# GMSL_DESERIALIZER.net
KiCad netlist of a schematic drawn in Altium Designer
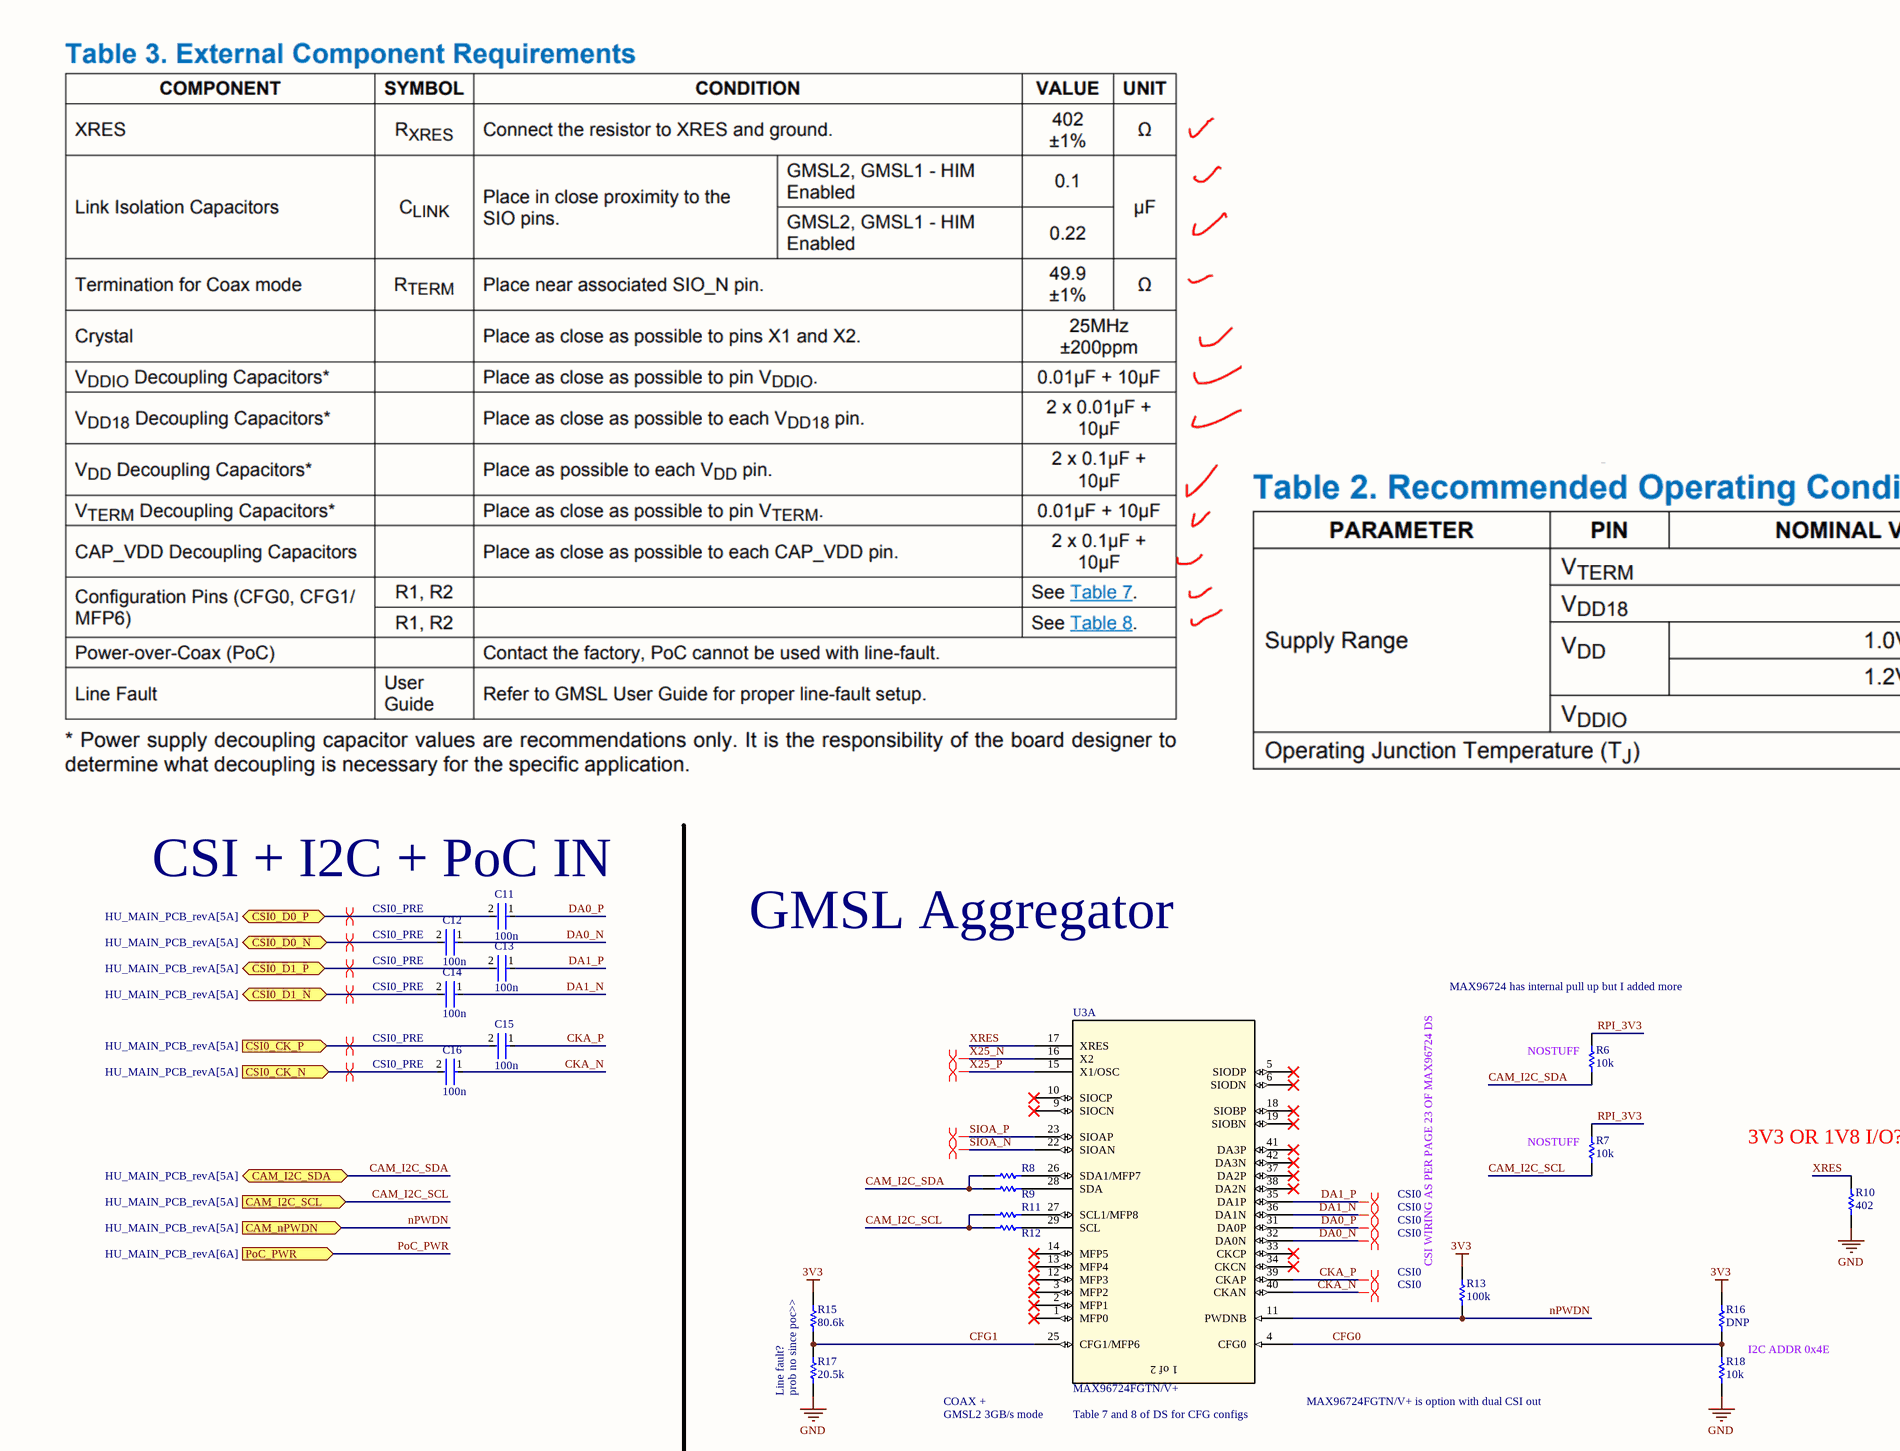
[diagram p0: GMSL_DESERIALIZER.SchDoc, top left]
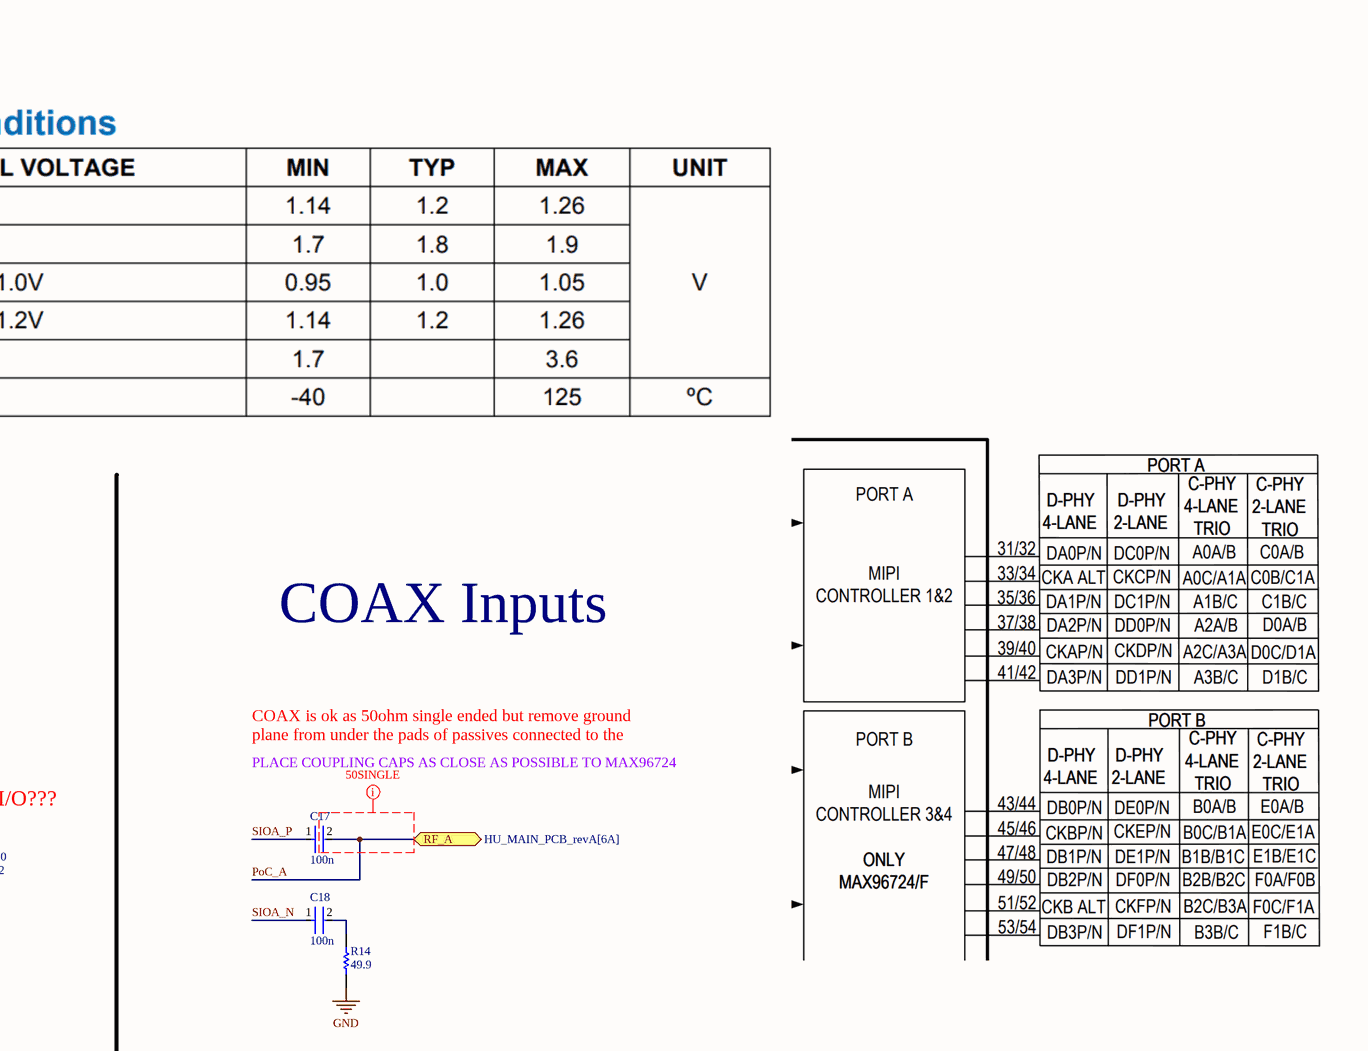
[diagram p1: GMSL_DESERIALIZER.SchDoc, top right]
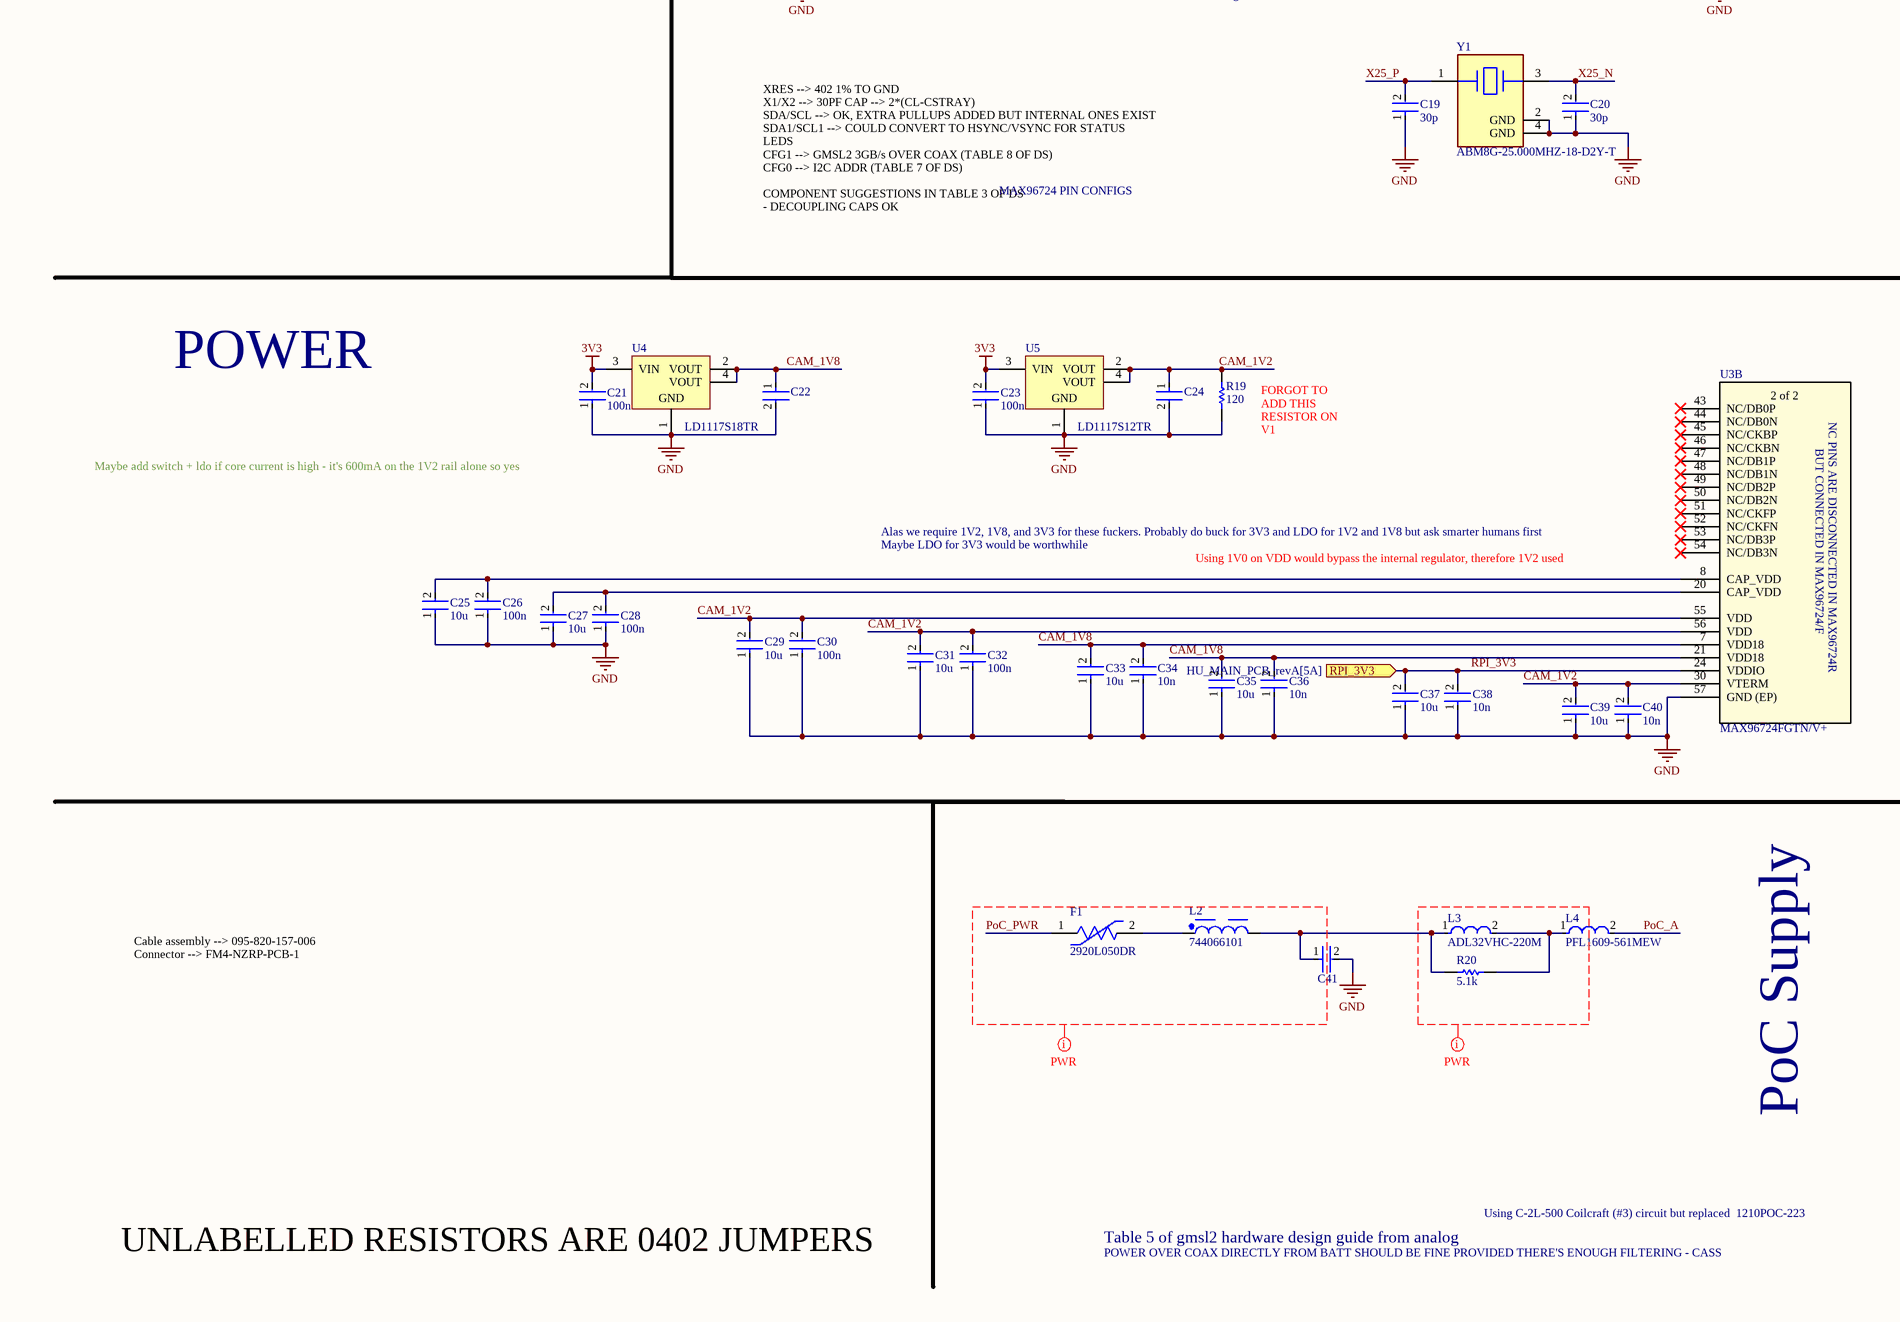
[diagram p2: GMSL_DESERIALIZER.SchDoc, bottom left]
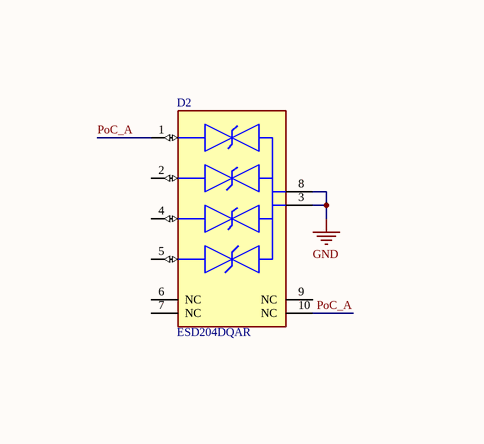
[diagram p3: GMSL_DESERIALIZER.SchDoc, bottom right]

(export (version "E")
  (design (tool "Eeschema 10.0.6"))
  (components
    (comp (ref "C11")
      (value "100n")
      (footprint "FP-0402-L_1_0_0_05-W_0_5-IPC_A")
      (description "LARGE PADS, 0402 CAP, CHANGE COMMENT TO MATCH REAL P/N")
      (libsource (lib "Space Concordia") (part "b4654b650e69147ec39a6b967a45e02"))
    )
    (comp (ref "C12")
      (value "100n")
      (footprint "FP-0402-L_1_0_0_05-W_0_5-IPC_A")
      (description "LARGE PADS, 0402 CAP, CHANGE COMMENT TO MATCH REAL P/N")
      (libsource (lib "Space Concordia") (part "b4654b650e69147ec39a6b967a45e02"))
    )
    (comp (ref "C13")
      (value "100n")
      (footprint "FP-0402-L_1_0_0_05-W_0_5-IPC_A")
      (description "LARGE PADS, 0402 CAP, CHANGE COMMENT TO MATCH REAL P/N")
      (libsource (lib "Space Concordia") (part "b4654b650e69147ec39a6b967a45e02"))
    )
    (comp (ref "C14")
      (value "100n")
      (footprint "FP-0402-L_1_0_0_05-W_0_5-IPC_A")
      (description "LARGE PADS, 0402 CAP, CHANGE COMMENT TO MATCH REAL P/N")
      (libsource (lib "Space Concordia") (part "b4654b650e69147ec39a6b967a45e02"))
    )
    (comp (ref "C15")
      (value "100n")
      (footprint "FP-0402-L_1_0_0_05-W_0_5-IPC_A")
      (description "LARGE PADS, 0402 CAP, CHANGE COMMENT TO MATCH REAL P/N")
      (libsource (lib "Space Concordia") (part "b4654b650e69147ec39a6b967a45e02"))
    )
    (comp (ref "C16")
      (value "100n")
      (footprint "FP-0402-L_1_0_0_05-W_0_5-IPC_A")
      (description "LARGE PADS, 0402 CAP, CHANGE COMMENT TO MATCH REAL P/N")
      (libsource (lib "Space Concordia") (part "b4654b650e69147ec39a6b967a45e02"))
    )
    (comp (ref "C17")
      (value "100n")
      (footprint "FP-0402-L_1_0_0_05-W_0_5-IPC_A")
      (description "LARGE PADS, 0402 CAP, CHANGE COMMENT TO MATCH REAL P/N")
      (libsource (lib "Space Concordia") (part "b4654b650e69147ec39a6b967a45e02"))
    )
    (comp (ref "C18")
      (value "100n")
      (footprint "FP-0402-L_1_0_0_05-W_0_5-IPC_A")
      (description "LARGE PADS, 0402 CAP, CHANGE COMMENT TO MATCH REAL P/N")
      (libsource (lib "Space Concordia") (part "b4654b650e69147ec39a6b967a45e02"))
    )
    (comp (ref "C19")
      (value "30p")
      (footprint "FP-0402-L_1_0_0_05-W_0_5-IPC_A")
      (description "LARGE PADS, 0402 CAP, CHANGE COMMENT TO MATCH REAL P/N")
      (libsource (lib "Space Concordia") (part "b4654b650e69147ec39a6b967a45e02"))
    )
    (comp (ref "C20")
      (value "30p")
      (footprint "FP-0402-L_1_0_0_05-W_0_5-IPC_A")
      (description "LARGE PADS, 0402 CAP, CHANGE COMMENT TO MATCH REAL P/N")
      (libsource (lib "Space Concordia") (part "b4654b650e69147ec39a6b967a45e02"))
    )
    (comp (ref "C21")
      (value "100n")
      (footprint "FP-0402-L_1_0_0_05-W_0_5-IPC_A")
      (description "LARGE PADS, 0402 CAP, CHANGE COMMENT TO MATCH REAL P/N")
      (libsource (lib "Space Concordia") (part "b4654b650e69147ec39a6b967a45e02"))
    )
    (comp (ref "C22")
      (value "GRM188R60J106ME47D")
      (footprint "FP-GRM188-0_1-e0_2_0_55-IPC_A")
      (description "Chip Multilayer Ceramic Capacitors for General Purpose, 0603, 10uF, X5R, 15%, 20%, 6.3V")
      (fields (field (name "VOLTAGE") "6.3V") (field (name "TOLERANCE") "20%"))
      (libsource (lib "Altium Content Vault") (part "02cd4be3c70576c341d710602a673aa"))
    )
    (comp (ref "C23")
      (value "100n")
      (footprint "FP-0402-L_1_0_0_05-W_0_5-IPC_A")
      (description "LARGE PADS, 0402 CAP, CHANGE COMMENT TO MATCH REAL P/N")
      (libsource (lib "Space Concordia") (part "b4654b650e69147ec39a6b967a45e02"))
    )
    (comp (ref "C24")
      (value "GRM188R60J106ME47D")
      (footprint "FP-GRM188-0_1-e0_2_0_55-IPC_A")
      (description "Chip Multilayer Ceramic Capacitors for General Purpose, 0603, 10uF, X5R, 15%, 20%, 6.3V")
      (fields (field (name "VOLTAGE") "6.3V") (field (name "TOLERANCE") "20%"))
      (libsource (lib "Altium Content Vault") (part "02cd4be3c70576c341d710602a673aa"))
    )
    (comp (ref "C25")
      (value "10u")
      (footprint "FP-0402-L_1_0_0_05-W_0_5-IPC_A")
      (description "LARGE PADS, 0402 CAP, CHANGE COMMENT TO MATCH REAL P/N")
      (libsource (lib "Space Concordia") (part "b4654b650e69147ec39a6b967a45e02"))
    )
    (comp (ref "C26")
      (value "100n")
      (footprint "FP-0402-L_1_0_0_05-W_0_5-IPC_A")
      (description "LARGE PADS, 0402 CAP, CHANGE COMMENT TO MATCH REAL P/N")
      (libsource (lib "Space Concordia") (part "b4654b650e69147ec39a6b967a45e02"))
    )
    (comp (ref "C27")
      (value "10u")
      (footprint "FP-0402-L_1_0_0_05-W_0_5-IPC_A")
      (description "LARGE PADS, 0402 CAP, CHANGE COMMENT TO MATCH REAL P/N")
      (libsource (lib "Space Concordia") (part "b4654b650e69147ec39a6b967a45e02"))
    )
    (comp (ref "C28")
      (value "100n")
      (footprint "FP-0402-L_1_0_0_05-W_0_5-IPC_A")
      (description "LARGE PADS, 0402 CAP, CHANGE COMMENT TO MATCH REAL P/N")
      (libsource (lib "Space Concordia") (part "b4654b650e69147ec39a6b967a45e02"))
    )
    (comp (ref "C29")
      (value "10u")
      (footprint "FP-0402-L_1_0_0_05-W_0_5-IPC_A")
      (description "LARGE PADS, 0402 CAP, CHANGE COMMENT TO MATCH REAL P/N")
      (libsource (lib "Space Concordia") (part "b4654b650e69147ec39a6b967a45e02"))
    )
    (comp (ref "C30")
      (value "100n")
      (footprint "FP-0402-L_1_0_0_05-W_0_5-IPC_A")
      (description "LARGE PADS, 0402 CAP, CHANGE COMMENT TO MATCH REAL P/N")
      (libsource (lib "Space Concordia") (part "b4654b650e69147ec39a6b967a45e02"))
    )
    (comp (ref "C31")
      (value "10u")
      (footprint "FP-0402-L_1_0_0_05-W_0_5-IPC_A")
      (description "LARGE PADS, 0402 CAP, CHANGE COMMENT TO MATCH REAL P/N")
      (libsource (lib "Space Concordia") (part "b4654b650e69147ec39a6b967a45e02"))
    )
    (comp (ref "C32")
      (value "100n")
      (footprint "FP-0402-L_1_0_0_05-W_0_5-IPC_A")
      (description "LARGE PADS, 0402 CAP, CHANGE COMMENT TO MATCH REAL P/N")
      (libsource (lib "Space Concordia") (part "b4654b650e69147ec39a6b967a45e02"))
    )
    (comp (ref "C33")
      (value "10u")
      (footprint "FP-0402-L_1_0_0_05-W_0_5-IPC_A")
      (description "LARGE PADS, 0402 CAP, CHANGE COMMENT TO MATCH REAL P/N")
      (libsource (lib "Space Concordia") (part "b4654b650e69147ec39a6b967a45e02"))
    )
    (comp (ref "C34")
      (value "10n")
      (footprint "FP-0402-L_1_0_0_05-W_0_5-IPC_A")
      (description "LARGE PADS, 0402 CAP, CHANGE COMMENT TO MATCH REAL P/N")
      (libsource (lib "Space Concordia") (part "b4654b650e69147ec39a6b967a45e02"))
    )
    (comp (ref "C35")
      (value "10u")
      (footprint "FP-0402-L_1_0_0_05-W_0_5-IPC_A")
      (description "LARGE PADS, 0402 CAP, CHANGE COMMENT TO MATCH REAL P/N")
      (libsource (lib "Space Concordia") (part "b4654b650e69147ec39a6b967a45e02"))
    )
    (comp (ref "C36")
      (value "10n")
      (footprint "FP-0402-L_1_0_0_05-W_0_5-IPC_A")
      (description "LARGE PADS, 0402 CAP, CHANGE COMMENT TO MATCH REAL P/N")
      (libsource (lib "Space Concordia") (part "b4654b650e69147ec39a6b967a45e02"))
    )
    (comp (ref "C37")
      (value "10u")
      (footprint "FP-0402-L_1_0_0_05-W_0_5-IPC_A")
      (description "LARGE PADS, 0402 CAP, CHANGE COMMENT TO MATCH REAL P/N")
      (libsource (lib "Space Concordia") (part "b4654b650e69147ec39a6b967a45e02"))
    )
    (comp (ref "C38")
      (value "10n")
      (footprint "FP-0402-L_1_0_0_05-W_0_5-IPC_A")
      (description "LARGE PADS, 0402 CAP, CHANGE COMMENT TO MATCH REAL P/N")
      (libsource (lib "Space Concordia") (part "b4654b650e69147ec39a6b967a45e02"))
    )
    (comp (ref "C39")
      (value "10u")
      (footprint "FP-0402-L_1_0_0_05-W_0_5-IPC_A")
      (description "LARGE PADS, 0402 CAP, CHANGE COMMENT TO MATCH REAL P/N")
      (libsource (lib "Space Concordia") (part "b4654b650e69147ec39a6b967a45e02"))
    )
    (comp (ref "C40")
      (value "10n")
      (footprint "FP-0402-L_1_0_0_05-W_0_5-IPC_A")
      (description "LARGE PADS, 0402 CAP, CHANGE COMMENT TO MATCH REAL P/N")
      (libsource (lib "Space Concordia") (part "b4654b650e69147ec39a6b967a45e02"))
    )
    (comp (ref "C41")
      (value "GRM21BR61E226ME44L")
      (footprint "FP-GRM21B-0_2-e0_2_0_7-IPC_B")
      (description "Chip Multilayer Ceramic Capacitors for General Purpose, 0805, 22uF, X5R, 15%, 20%, 25V")
      (fields (field (name "TOLERANCE") "20%") (field (name "VOLTAGE") "25V"))
      (libsource (lib "Altium Content Vault") (part "b4654b650e69147ec39a6b967a45e02"))
    )
    (comp (ref "D2")
      (value "ESD204DQAR")
      (footprint "FP-DQA0010A-MFG")
      (description "4-CHANNEL LOW-CAPACITANCE SURGE")
      (fields
        (field (name "MANUFACTURER") "Texas Instruments")
        (field (name "OCTOPART") "https://octopart.com/esd204dqar-texas+instruments-89917476")
      )
      (libsource (lib "Altium Content Vault") (part "1465e58c1818c7767b55926832f0bf5"))
    )
    (comp (ref "F1")
      (value "2920L050DR")
      (footprint "FP-2920L050DR-MFG")
      (description "PTC RESET FUSE 60V 500MA 2920")
      (libsource (lib "Altium Content Vault") (part "1c6d77a0208143737455a0c7eb396be"))
    )
    (comp (ref "L2")
      (value "744066101")
      (footprint "WE-TPC_1038")
      (fields (field (name "TOLERANCE") "30%"))
      (libsource (lib "Altium Content Vault") (part "Inductor - 2"))
    )
    (comp (ref "L3")
      (value "ADL32VHC-220M")
      (footprint "FP-1210POC-MFG")
      (description "NOT COILCRAFT - ACTUAL P# --> ADL32VHC-220M\r\n - Power Injection Chokes for PoC")
      (fields
        (field (name "MANUFACTURER") "coilcraft")
        (field (name "OCTOPART") "https://octopart.com/1210poc-223mrc-coilcraft-103207315")
      )
      (libsource (lib "Altium Content Vault") (part "725321dda6339637d4d059423bc1c3c"))
    )
    (comp (ref "L4")
      (value "PFL1609-561MEW")
      (footprint "FP-PFL1609-MFG")
      (description "Fixed Inductors PFL1609 Low Profile 0.56 uH 20 % 1.4 A")
      (fields (field (name "MANUFACTURER") "coilcraft") (field (name "TOLERANCE") "20%"))
      (libsource (lib "Altium Content Vault") (part "725321dda6339637d4d059423bc1c3c"))
    )
    (comp (ref "R6")
      (value "10k")
      (footprint "R0603B")
      (description "Resistor")
      (libsource (lib "Space Concordia") (part "Resistor"))
    )
    (comp (ref "R7")
      (value "10k")
      (footprint "R0603B")
      (description "Resistor")
      (libsource (lib "Space Concordia") (part "Resistor"))
    )
    (comp (ref "R8")
      (value "0402 JUMPER")
      (footprint "RESC1005X40X25ML05T05")
      (description "READ THE NAME")
      (libsource (lib "Space Concordia") (part "CMP-009-00206-2"))
    )
    (comp (ref "R9")
      (value "0402 JUMPER")
      (footprint "RESC1005X40X25ML05T05")
      (description "READ THE NAME")
      (libsource (lib "Space Concordia") (part "CMP-009-00206-2"))
    )
    (comp (ref "R10")
      (value "402")
      (footprint "R0603B")
      (description "Resistor")
      (libsource (lib "Space Concordia") (part "Resistor"))
    )
    (comp (ref "R11")
      (value "0402 JUMPER")
      (footprint "RESC1005X40X25ML05T05")
      (description "READ THE NAME")
      (libsource (lib "Space Concordia") (part "CMP-009-00206-2"))
    )
    (comp (ref "R12")
      (value "0402 JUMPER")
      (footprint "RESC1005X40X25ML05T05")
      (description "READ THE NAME")
      (libsource (lib "Space Concordia") (part "CMP-009-00206-2"))
    )
    (comp (ref "R13")
      (value "100k")
      (footprint "R0603B")
      (description "Resistor")
      (libsource (lib "Space Concordia") (part "Resistor"))
    )
    (comp (ref "R14")
      (value "49.9")
      (footprint "R0603B")
      (description "Resistor")
      (libsource (lib "Space Concordia") (part "Resistor"))
    )
    (comp (ref "R15")
      (value "80.6k")
      (footprint "R0603B")
      (description "Resistor")
      (libsource (lib "Space Concordia") (part "Resistor"))
    )
    (comp (ref "R16")
      (value "DNP")
      (footprint "R0603B")
      (description "Resistor")
      (libsource (lib "Space Concordia") (part "Resistor"))
    )
    (comp (ref "R17")
      (value "20.5k")
      (footprint "R0603B")
      (description "Resistor")
      (libsource (lib "Space Concordia") (part "Resistor"))
    )
    (comp (ref "R18")
      (value "10k")
      (footprint "R0603B")
      (description "Resistor")
      (libsource (lib "Space Concordia") (part "Resistor"))
    )
    (comp (ref "R19")
      (value "120")
      (footprint "R0603B")
      (description "Resistor")
      (libsource (lib "Space Concordia") (part "Resistor"))
    )
    (comp (ref "R20")
      (value "5.1k")
      (footprint "R0603B")
      (description "Resistor")
      (libsource (lib "Space Concordia") (part "Resistor"))
    )
    (comp (ref "U3")
      (value "MAX96724FGTN/V+")
      (footprint "MAX96724FGTN_V+-Footprint-1")
      (description "Quad Tunneling GMSL2/1 to CSI-2 Deserializer")
      (libsource (lib "") (part "MAX96724FGTN_V+-Symbol-1_1"))
    )
    (comp (ref "U4")
      (value "LD1117S18TR")
      (footprint "SOT-223_M")
      (description "Fixed Low Drop Positive Voltage Regulator, 1.8V, 4-Pin SOT-223, Tape and Reel")
      (libsource (lib "Altium Content Vault") (part "PM-REG-LD1117-SOT4"))
    )
    (comp (ref "U5")
      (value "LD1117S12TR")
      (footprint "SOT-223_M")
      (description "Fixed Low Drop Positive Voltage Regulator, 1.2V, 4-Pin SOT-223, Tape and Reel")
      (libsource (lib "Altium Content Vault") (part "PM-REG-LD1117-SOT4"))
    )
    (comp (ref "Y1")
      (value "ABM8G-25.000MHZ-18-D2Y-T")
      (footprint "FP-ABM8G-MFG")
      (description "Crystal 25MHz ±20ppm (Tol) ±30ppm (Stability) 18pF FUND 60Ω 4-Pin SMD T/R")
      (fields (field (name "TOLERANCE") "20ppm"))
      (libsource (lib "Altium Content Vault") (part "48e526d86b7f2615d98721063c72f49"))
    )
  )
  (nets
    (net (code "1") (name "/CAM_1V2") (class "Default")
      (node (ref "C24") (pin "1") (pinfunction "1_1") (pintype "passive"))
      (node (ref "C29") (pin "2") (pinfunction "2_2") (pintype "passive"))
      (node (ref "C30") (pin "2") (pinfunction "2_2") (pintype "passive"))
      (node (ref "C31") (pin "2") (pinfunction "2_2") (pintype "passive"))
      (node (ref "C32") (pin "2") (pinfunction "2_2") (pintype "passive"))
      (node (ref "C39") (pin "2") (pinfunction "2_2") (pintype "passive"))
      (node (ref "C40") (pin "2") (pinfunction "2_2") (pintype "passive"))
      (node (ref "R19") (pin "1") (pinfunction "1_1") (pintype "passive"))
      (node (ref "U3") (pin "30") (pinfunction "VTERM_30") (pintype "power_in"))
      (node (ref "U3") (pin "55") (pinfunction "VDD_55") (pintype "power_in"))
      (node (ref "U3") (pin "56") (pinfunction "VDD_56") (pintype "power_in"))
      (node (ref "U5") (pin "2") (pinfunction "VOUT_2") (pintype "power_in"))
      (node (ref "U5") (pin "4") (pinfunction "VOUT_4") (pintype "power_in"))
    )
    (net (code "2") (name "/CAM_1V8") (class "Default")
      (node (ref "C22") (pin "1") (pinfunction "1_1") (pintype "passive"))
      (node (ref "C33") (pin "2") (pinfunction "2_2") (pintype "passive"))
      (node (ref "C34") (pin "2") (pinfunction "2_2") (pintype "passive"))
      (node (ref "C35") (pin "2") (pinfunction "2_2") (pintype "passive"))
      (node (ref "C36") (pin "2") (pinfunction "2_2") (pintype "passive"))
      (node (ref "U3") (pin "21") (pinfunction "VDD18_21") (pintype "power_in"))
      (node (ref "U3") (pin "7") (pinfunction "VDD18_7") (pintype "power_in"))
      (node (ref "U4") (pin "2") (pinfunction "VOUT_2") (pintype "power_in"))
      (node (ref "U4") (pin "4") (pinfunction "VOUT_4") (pintype "power_in"))
    )
    (net (code "3") (name "/CAM_I2C_SCL") (class "Default")
      (node (ref "R11") (pin "1") (pinfunction "1_1") (pintype "passive"))
      (node (ref "R12") (pin "1") (pinfunction "1_1") (pintype "passive"))
      (node (ref "R7") (pin "1") (pinfunction "1_1") (pintype "passive"))
    )
    (net (code "4") (name "/CAM_I2C_SDA") (class "Default")
      (node (ref "R6") (pin "1") (pinfunction "1_1") (pintype "passive"))
      (node (ref "R8") (pin "1") (pinfunction "1_1") (pintype "passive"))
      (node (ref "R9") (pin "1") (pinfunction "1_1") (pintype "passive"))
    )
    (net (code "5") (name "/CFG0") (class "Default")
      (node (ref "R16") (pin "1") (pinfunction "1_1") (pintype "passive"))
      (node (ref "R18") (pin "2") (pinfunction "2_2") (pintype "passive"))
      (node (ref "U3") (pin "4") (pinfunction "CFG0_4") (pintype "input"))
    )
    (net (code "6") (name "/CFG1") (class "Default")
      (node (ref "R15") (pin "1") (pinfunction "1_1") (pintype "passive"))
      (node (ref "R17") (pin "2") (pinfunction "2_2") (pintype "passive"))
      (node (ref "U3") (pin "25") (pinfunction "CFG1/MFP6_25") (pintype "bidirectional"))
    )
    (net (code "7") (name "/CKA_N") (class "Default")
      (node (ref "C16") (pin "1") (pinfunction "1_1") (pintype "passive"))
      (node (ref "U3") (pin "40") (pinfunction "CKAN_40") (pintype "bidirectional"))
    )
    (net (code "8") (name "/CKA_P") (class "Default")
      (node (ref "C15") (pin "1") (pinfunction "1_1") (pintype "passive"))
      (node (ref "U3") (pin "39") (pinfunction "CKAP_39") (pintype "bidirectional"))
    )
    (net (code "9") (name "/CSI0_CK_N") (class "Default")
      (node (ref "C16") (pin "2") (pinfunction "2_2") (pintype "passive"))
    )
    (net (code "10") (name "/CSI0_CK_P") (class "Default")
      (node (ref "C15") (pin "2") (pinfunction "2_2") (pintype "passive"))
    )
    (net (code "11") (name "/CSI0_D0_N") (class "Default")
      (node (ref "C12") (pin "2") (pinfunction "2_2") (pintype "passive"))
    )
    (net (code "12") (name "/CSI0_D0_P") (class "Default")
      (node (ref "C11") (pin "2") (pinfunction "2_2") (pintype "passive"))
    )
    (net (code "13") (name "/CSI0_D1_N") (class "Default")
      (node (ref "C14") (pin "2") (pinfunction "2_2") (pintype "passive"))
    )
    (net (code "14") (name "/CSI0_D1_P") (class "Default")
      (node (ref "C13") (pin "2") (pinfunction "2_2") (pintype "passive"))
    )
    (net (code "15") (name "/DA0_N") (class "Default")
      (node (ref "C12") (pin "1") (pinfunction "1_1") (pintype "passive"))
      (node (ref "U3") (pin "32") (pinfunction "DA0N_32") (pintype "bidirectional"))
    )
    (net (code "16") (name "/DA0_P") (class "Default")
      (node (ref "C11") (pin "1") (pinfunction "1_1") (pintype "passive"))
      (node (ref "U3") (pin "31") (pinfunction "DA0P_31") (pintype "bidirectional"))
    )
    (net (code "17") (name "/DA1_N") (class "Default")
      (node (ref "C14") (pin "1") (pinfunction "1_1") (pintype "passive"))
      (node (ref "U3") (pin "36") (pinfunction "DA1N_36") (pintype "bidirectional"))
    )
    (net (code "18") (name "/DA1_P") (class "Default")
      (node (ref "C13") (pin "1") (pinfunction "1_1") (pintype "passive"))
      (node (ref "U3") (pin "35") (pinfunction "DA1P_35") (pintype "bidirectional"))
    )
    (net (code "19") (name "/PoC_A") (class "Default")
      (node (ref "C17") (pin "2") (pinfunction "2_2") (pintype "passive"))
      (node (ref "D2") (pin "1") (pinfunction "IO1_1") (pintype "bidirectional"))
      (node (ref "D2") (pin "10") (pinfunction "NC_10") (pintype "passive"))
      (node (ref "L4") (pin "2") (pinfunction "2_2") (pintype "passive"))
    )
    (net (code "20") (name "/PoC_PWR") (class "Default")
      (node (ref "F1") (pin "1") (pinfunction "1_1") (pintype "passive"))
    )
    (net (code "21") (name "/RPI_3V3") (class "Default")
      (node (ref "C37") (pin "2") (pinfunction "2_2") (pintype "passive"))
      (node (ref "C38") (pin "2") (pinfunction "2_2") (pintype "passive"))
      (node (ref "R6") (pin "2") (pinfunction "2_2") (pintype "passive"))
      (node (ref "R7") (pin "2") (pinfunction "2_2") (pintype "passive"))
      (node (ref "U3") (pin "24") (pinfunction "VDDIO_24") (pintype "power_in"))
    )
    (net (code "22") (name "/SIOA_N") (class "Default")
      (node (ref "C18") (pin "1") (pinfunction "1_1") (pintype "passive"))
      (node (ref "U3") (pin "22") (pinfunction "SIOAN_22") (pintype "bidirectional"))
    )
    (net (code "23") (name "/SIOA_P") (class "Default")
      (node (ref "C17") (pin "1") (pinfunction "1_1") (pintype "passive"))
      (node (ref "U3") (pin "23") (pinfunction "SIOAP_23") (pintype "bidirectional"))
    )
    (net (code "24") (name "/X25_N") (class "Default")
      (node (ref "C20") (pin "2") (pinfunction "2_2") (pintype "passive"))
      (node (ref "U3") (pin "16") (pinfunction "X2_16") (pintype "passive"))
      (node (ref "Y1") (pin "3") (pinfunction "3_3") (pintype "passive"))
    )
    (net (code "25") (name "/X25_P") (class "Default")
      (node (ref "C19") (pin "2") (pinfunction "2_2") (pintype "passive"))
      (node (ref "U3") (pin "15") (pinfunction "X1/OSC_15") (pintype "passive"))
      (node (ref "Y1") (pin "1") (pinfunction "1_1") (pintype "passive"))
    )
    (net (code "26") (name "/XRES") (class "Default")
      (node (ref "R10") (pin "2") (pinfunction "2_2") (pintype "passive"))
      (node (ref "U3") (pin "17") (pinfunction "XRES_17") (pintype "passive"))
    )
    (net (code "27") (name "/nPWDN") (class "Default")
      (node (ref "R13") (pin "1") (pinfunction "1_1") (pintype "passive"))
      (node (ref "U3") (pin "11") (pinfunction "PWDNB_11") (pintype "input"))
    )
    (net (code "28") (name "3V3") (class "Default")
      (node (ref "C21") (pin "2") (pinfunction "2_2") (pintype "passive"))
      (node (ref "C23") (pin "2") (pinfunction "2_2") (pintype "passive"))
      (node (ref "R13") (pin "2") (pinfunction "2_2") (pintype "passive"))
      (node (ref "R15") (pin "2") (pinfunction "2_2") (pintype "passive"))
      (node (ref "R16") (pin "2") (pinfunction "2_2") (pintype "passive"))
      (node (ref "U4") (pin "3") (pinfunction "VIN_3") (pintype "power_in"))
      (node (ref "U5") (pin "3") (pinfunction "VIN_3") (pintype "power_in"))
    )
    (net (code "29") (name "GND") (class "Default")
      (node (ref "C19") (pin "1") (pinfunction "1_1") (pintype "passive"))
      (node (ref "C20") (pin "1") (pinfunction "1_1") (pintype "passive"))
      (node (ref "C21") (pin "1") (pinfunction "1_1") (pintype "passive"))
      (node (ref "C22") (pin "2") (pinfunction "2_2") (pintype "passive"))
      (node (ref "C23") (pin "1") (pinfunction "1_1") (pintype "passive"))
      (node (ref "C24") (pin "2") (pinfunction "2_2") (pintype "passive"))
      (node (ref "C25") (pin "1") (pinfunction "1_1") (pintype "passive"))
      (node (ref "C26") (pin "1") (pinfunction "1_1") (pintype "passive"))
      (node (ref "C27") (pin "1") (pinfunction "1_1") (pintype "passive"))
      (node (ref "C28") (pin "1") (pinfunction "1_1") (pintype "passive"))
      (node (ref "C29") (pin "1") (pinfunction "1_1") (pintype "passive"))
      (node (ref "C30") (pin "1") (pinfunction "1_1") (pintype "passive"))
      (node (ref "C31") (pin "1") (pinfunction "1_1") (pintype "passive"))
      (node (ref "C32") (pin "1") (pinfunction "1_1") (pintype "passive"))
      (node (ref "C33") (pin "1") (pinfunction "1_1") (pintype "passive"))
      (node (ref "C34") (pin "1") (pinfunction "1_1") (pintype "passive"))
      (node (ref "C35") (pin "1") (pinfunction "1_1") (pintype "passive"))
      (node (ref "C36") (pin "1") (pinfunction "1_1") (pintype "passive"))
      (node (ref "C37") (pin "1") (pinfunction "1_1") (pintype "passive"))
      (node (ref "C38") (pin "1") (pinfunction "1_1") (pintype "passive"))
      (node (ref "C39") (pin "1") (pinfunction "1_1") (pintype "passive"))
      (node (ref "C40") (pin "1") (pinfunction "1_1") (pintype "passive"))
      (node (ref "C41") (pin "2") (pinfunction "2_2") (pintype "passive"))
      (node (ref "D2") (pin "3") (pinfunction "GND_3") (pintype "power_in"))
      (node (ref "D2") (pin "8") (pinfunction "GND_8") (pintype "power_in"))
      (node (ref "R10") (pin "1") (pinfunction "1_1") (pintype "passive"))
      (node (ref "R14") (pin "1") (pinfunction "1_1") (pintype "passive"))
      (node (ref "R17") (pin "1") (pinfunction "1_1") (pintype "passive"))
      (node (ref "R18") (pin "1") (pinfunction "1_1") (pintype "passive"))
      (node (ref "R19") (pin "2") (pinfunction "2_2") (pintype "passive"))
      (node (ref "U3") (pin "57") (pinfunction "GND_(EP)_57") (pintype "power_in"))
      (node (ref "U4") (pin "1") (pinfunction "GND_1") (pintype "power_in"))
      (node (ref "U5") (pin "1") (pinfunction "GND_1") (pintype "power_in"))
      (node (ref "Y1") (pin "2") (pinfunction "GND_2") (pintype "power_in"))
      (node (ref "Y1") (pin "4") (pinfunction "GND_4") (pintype "power_in"))
    )
    (net (code "30") (name "Net-(C18-Pad2)") (class "Default")
      (node (ref "C18") (pin "2") (pinfunction "2_2") (pintype "passive"))
      (node (ref "R14") (pin "2") (pinfunction "2_2") (pintype "passive"))
    )
    (net (code "31") (name "Net-(C25-Pad2)") (class "Default")
      (node (ref "C25") (pin "2") (pinfunction "2_2") (pintype "passive"))
      (node (ref "C26") (pin "2") (pinfunction "2_2") (pintype "passive"))
      (node (ref "U3") (pin "8") (pinfunction "CAP_VDD_8") (pintype "power_in"))
    )
    (net (code "32") (name "Net-(C27-Pad2)") (class "Default")
      (node (ref "C27") (pin "2") (pinfunction "2_2") (pintype "passive"))
      (node (ref "C28") (pin "2") (pinfunction "2_2") (pintype "passive"))
      (node (ref "U3") (pin "20") (pinfunction "CAP_VDD_20") (pintype "power_in"))
    )
    (net (code "33") (name "Net-(C41-Pad1)") (class "Default")
      (node (ref "C41") (pin "1") (pinfunction "1_1") (pintype "passive"))
      (node (ref "L2") (pin "2") (pinfunction "2_2") (pintype "passive"))
      (node (ref "L3") (pin "1") (pinfunction "1_1") (pintype "passive"))
      (node (ref "R20") (pin "2") (pinfunction "2_2") (pintype "passive"))
    )
    (net (code "34") (name "Net-(F1-Pad2)") (class "Default")
      (node (ref "F1") (pin "2") (pinfunction "2_2") (pintype "passive"))
      (node (ref "L2") (pin "1") (pinfunction "1_1") (pintype "passive"))
    )
    (net (code "35") (name "Net-(L3-Pad2)") (class "Default")
      (node (ref "L3") (pin "2") (pinfunction "2_2") (pintype "passive"))
      (node (ref "L4") (pin "1") (pinfunction "1_1") (pintype "passive"))
      (node (ref "R20") (pin "1") (pinfunction "1_1") (pintype "passive"))
    )
    (net (code "36") (name "Net-(U3A-SCL)") (class "Default")
      (node (ref "R12") (pin "2") (pinfunction "2_2") (pintype "passive"))
      (node (ref "U3") (pin "29") (pinfunction "SCL_29") (pintype "passive"))
    )
    (net (code "37") (name "Net-(U3A-SCL1{slash}MFP8)") (class "Default")
      (node (ref "R11") (pin "2") (pinfunction "2_2") (pintype "passive"))
      (node (ref "U3") (pin "27") (pinfunction "SCL1/MFP8_27") (pintype "bidirectional"))
    )
    (net (code "38") (name "Net-(U3A-SDA)") (class "Default")
      (node (ref "R9") (pin "2") (pinfunction "2_2") (pintype "passive"))
      (node (ref "U3") (pin "28") (pinfunction "SDA_28") (pintype "passive"))
    )
    (net (code "39") (name "Net-(U3A-SDA1{slash}MFP7)") (class "Default")
      (node (ref "R8") (pin "2") (pinfunction "2_2") (pintype "passive"))
      (node (ref "U3") (pin "26") (pinfunction "SDA1/MFP7_26") (pintype "bidirectional"))
    )
    (net (code "40") (name "unconnected-(D2-IO2-Pad2)") (class "Default")
      (node (ref "D2") (pin "2") (pinfunction "IO2_2") (pintype "bidirectional"))
    )
    (net (code "41") (name "unconnected-(D2-IO3-Pad4)") (class "Default")
      (node (ref "D2") (pin "4") (pinfunction "IO3_4") (pintype "bidirectional"))
    )
    (net (code "42") (name "unconnected-(D2-IO4-Pad5)") (class "Default")
      (node (ref "D2") (pin "5") (pinfunction "IO4_5") (pintype "bidirectional"))
    )
    (net (code "43") (name "unconnected-(D2-NC-Pad6)") (class "Default")
      (node (ref "D2") (pin "6") (pinfunction "NC_6") (pintype "passive"))
    )
    (net (code "44") (name "unconnected-(D2-NC-Pad7)") (class "Default")
      (node (ref "D2") (pin "7") (pinfunction "NC_7") (pintype "passive"))
    )
    (net (code "45") (name "unconnected-(D2-NC-Pad9)") (class "Default")
      (node (ref "D2") (pin "9") (pinfunction "NC_9") (pintype "passive"))
    )
    (net (code "46") (name "unconnected-(U3A-CKCN-Pad34)") (class "Default")
      (node (ref "U3") (pin "34") (pinfunction "CKCN_34") (pintype "bidirectional+no_connect"))
    )
    (net (code "47") (name "unconnected-(U3A-CKCP-Pad33)") (class "Default")
      (node (ref "U3") (pin "33") (pinfunction "CKCP_33") (pintype "bidirectional+no_connect"))
    )
    (net (code "48") (name "unconnected-(U3A-DA2N-Pad38)") (class "Default")
      (node (ref "U3") (pin "38") (pinfunction "DA2N_38") (pintype "bidirectional+no_connect"))
    )
    (net (code "49") (name "unconnected-(U3A-DA2P-Pad37)") (class "Default")
      (node (ref "U3") (pin "37") (pinfunction "DA2P_37") (pintype "bidirectional+no_connect"))
    )
    (net (code "50") (name "unconnected-(U3A-DA3N-Pad42)") (class "Default")
      (node (ref "U3") (pin "42") (pinfunction "DA3N_42") (pintype "bidirectional+no_connect"))
    )
    (net (code "51") (name "unconnected-(U3A-DA3P-Pad41)") (class "Default")
      (node (ref "U3") (pin "41") (pinfunction "DA3P_41") (pintype "bidirectional+no_connect"))
    )
    (net (code "52") (name "unconnected-(U3A-MFP0-Pad1)") (class "Default")
      (node (ref "U3") (pin "1") (pinfunction "MFP0_1") (pintype "bidirectional+no_connect"))
    )
    (net (code "53") (name "unconnected-(U3A-MFP1-Pad2)") (class "Default")
      (node (ref "U3") (pin "2") (pinfunction "MFP1_2") (pintype "bidirectional+no_connect"))
    )
    (net (code "54") (name "unconnected-(U3A-MFP2-Pad3)") (class "Default")
      (node (ref "U3") (pin "3") (pinfunction "MFP2_3") (pintype "bidirectional+no_connect"))
    )
    (net (code "55") (name "unconnected-(U3A-MFP3-Pad12)") (class "Default")
      (node (ref "U3") (pin "12") (pinfunction "MFP3_12") (pintype "bidirectional+no_connect"))
    )
    (net (code "56") (name "unconnected-(U3A-MFP4-Pad13)") (class "Default")
      (node (ref "U3") (pin "13") (pinfunction "MFP4_13") (pintype "bidirectional+no_connect"))
    )
    (net (code "57") (name "unconnected-(U3A-MFP5-Pad14)") (class "Default")
      (node (ref "U3") (pin "14") (pinfunction "MFP5_14") (pintype "bidirectional+no_connect"))
    )
    (net (code "58") (name "unconnected-(U3A-SIOBN-Pad19)") (class "Default")
      (node (ref "U3") (pin "19") (pinfunction "SIOBN_19") (pintype "bidirectional+no_connect"))
    )
    (net (code "59") (name "unconnected-(U3A-SIOBP-Pad18)") (class "Default")
      (node (ref "U3") (pin "18") (pinfunction "SIOBP_18") (pintype "bidirectional+no_connect"))
    )
    (net (code "60") (name "unconnected-(U3A-SIOCN-Pad9)") (class "Default")
      (node (ref "U3") (pin "9") (pinfunction "SIOCN_9") (pintype "bidirectional+no_connect"))
    )
    (net (code "61") (name "unconnected-(U3A-SIOCP-Pad10)") (class "Default")
      (node (ref "U3") (pin "10") (pinfunction "SIOCP_10") (pintype "bidirectional+no_connect"))
    )
    (net (code "62") (name "unconnected-(U3A-SIODN-Pad6)") (class "Default")
      (node (ref "U3") (pin "6") (pinfunction "SIODN_6") (pintype "bidirectional+no_connect"))
    )
    (net (code "63") (name "unconnected-(U3A-SIODP-Pad5)") (class "Default")
      (node (ref "U3") (pin "5") (pinfunction "SIODP_5") (pintype "bidirectional+no_connect"))
    )
    (net (code "64") (name "unconnected-(U3B-NC{slash}CKBN-Pad46)") (class "Default")
      (node (ref "U3") (pin "46") (pinfunction "NC/CKBN_46") (pintype "passive+no_connect"))
    )
    (net (code "65") (name "unconnected-(U3B-NC{slash}CKBP-Pad45)") (class "Default")
      (node (ref "U3") (pin "45") (pinfunction "NC/CKBP_45") (pintype "passive+no_connect"))
    )
    (net (code "66") (name "unconnected-(U3B-NC{slash}CKFN-Pad52)") (class "Default")
      (node (ref "U3") (pin "52") (pinfunction "NC/CKFN_52") (pintype "passive+no_connect"))
    )
    (net (code "67") (name "unconnected-(U3B-NC{slash}CKFP-Pad51)") (class "Default")
      (node (ref "U3") (pin "51") (pinfunction "NC/CKFP_51") (pintype "passive+no_connect"))
    )
    (net (code "68") (name "unconnected-(U3B-NC{slash}DB0N-Pad44)") (class "Default")
      (node (ref "U3") (pin "44") (pinfunction "NC/DB0N_44") (pintype "passive+no_connect"))
    )
    (net (code "69") (name "unconnected-(U3B-NC{slash}DB0P-Pad43)") (class "Default")
      (node (ref "U3") (pin "43") (pinfunction "NC/DB0P_43") (pintype "passive+no_connect"))
    )
    (net (code "70") (name "unconnected-(U3B-NC{slash}DB1N-Pad48)") (class "Default")
      (node (ref "U3") (pin "48") (pinfunction "NC/DB1N_48") (pintype "passive+no_connect"))
    )
    (net (code "71") (name "unconnected-(U3B-NC{slash}DB1P-Pad47)") (class "Default")
      (node (ref "U3") (pin "47") (pinfunction "NC/DB1P_47") (pintype "passive+no_connect"))
    )
    (net (code "72") (name "unconnected-(U3B-NC{slash}DB2N-Pad50)") (class "Default")
      (node (ref "U3") (pin "50") (pinfunction "NC/DB2N_50") (pintype "passive+no_connect"))
    )
    (net (code "73") (name "unconnected-(U3B-NC{slash}DB2P-Pad49)") (class "Default")
      (node (ref "U3") (pin "49") (pinfunction "NC/DB2P_49") (pintype "passive+no_connect"))
    )
    (net (code "74") (name "unconnected-(U3B-NC{slash}DB3N-Pad54)") (class "Default")
      (node (ref "U3") (pin "54") (pinfunction "NC/DB3N_54") (pintype "passive+no_connect"))
    )
    (net (code "75") (name "unconnected-(U3B-NC{slash}DB3P-Pad53)") (class "Default")
      (node (ref "U3") (pin "53") (pinfunction "NC/DB3P_53") (pintype "passive+no_connect"))
    )
  )
)
